# 15_RS485.net
KiCad netlist of a schematic drawn in Altium Designer
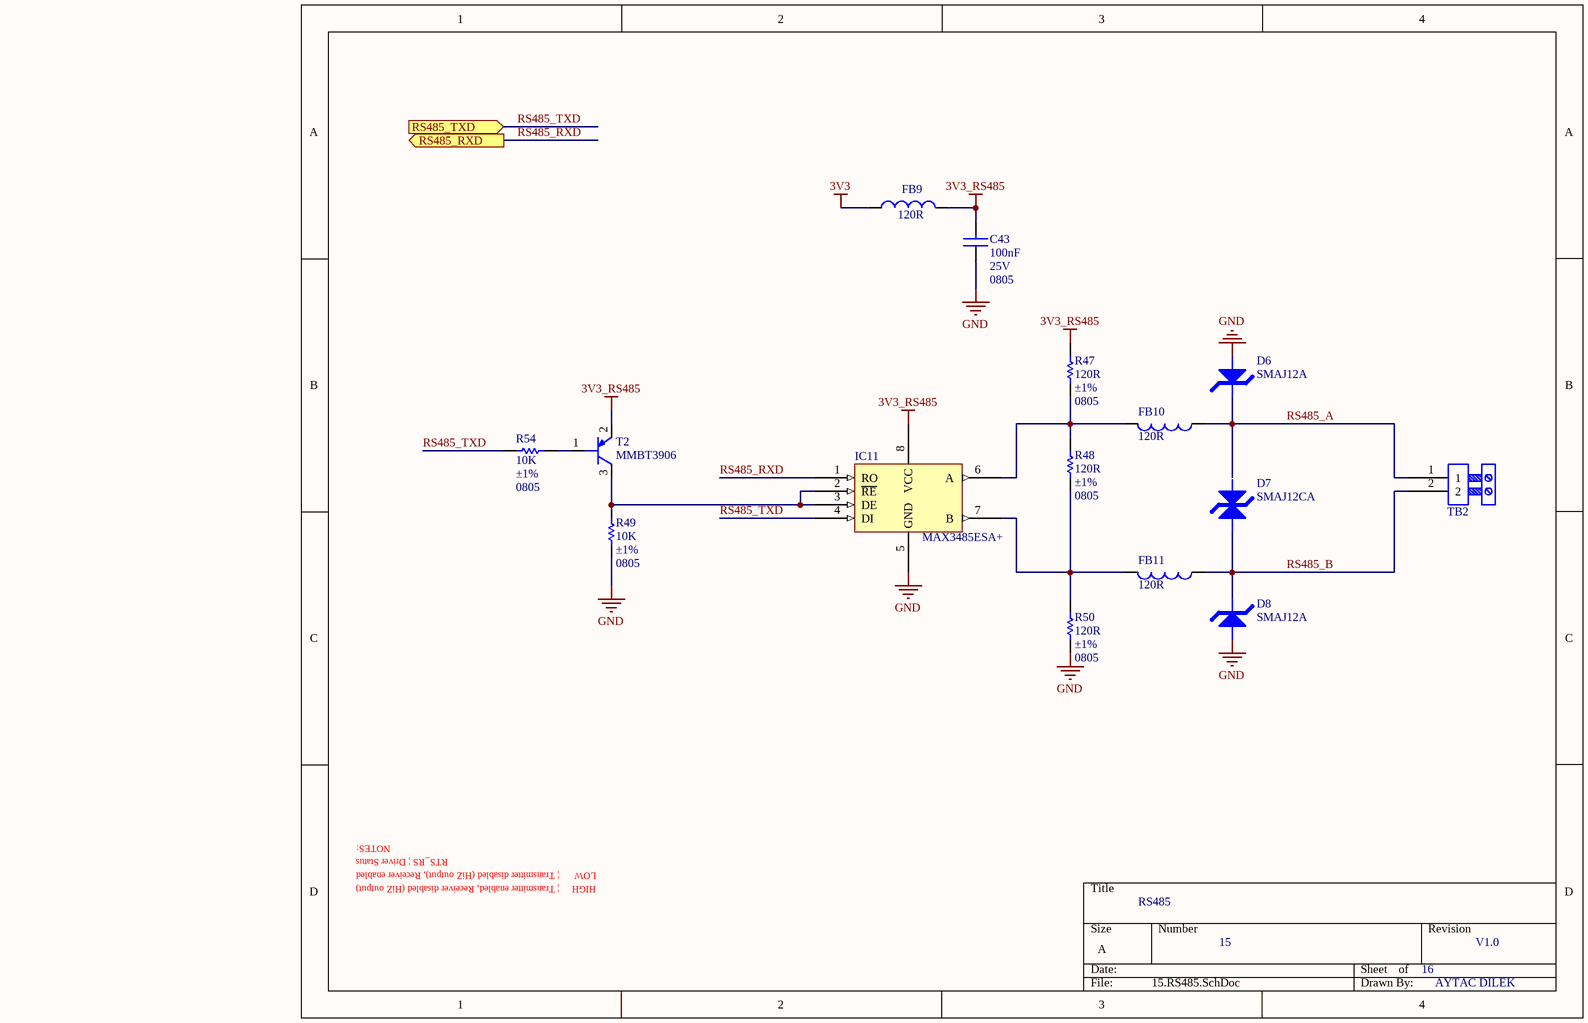
[diagram p0: 15.RS485.SchDoc]

(export (version "E")
  (design (tool "Eeschema 10.0.6"))
  (components
    (comp (ref "C43")
      (value "CAP_NP")
      (footprint "CAPC2012X100N_EIA0805")
      (description "CAP CER 0.1UF 25V X7R 0805")
      (fields
        (field (name "PART NUMBER") "SCAP00300093")
        (field (name "CAPACITANCE") "100nF")
        (field (name "TOLERANCE") "±10%")
        (field (name "VOLTAGE - RATED") "25V")
        (field (name "PACKAGE / CASE") "0805")
      )
      (libsource (lib "ComponentDatabase") (part "CAP_NP"))
    )
    (comp (ref "D6")
      (value "SMAJ12A")
      (footprint "DIOM5126X26N_DO-214AC_SMA")
      (description "TVS DIODE 12VWM 19.9VC SMA")
      (fields (field (name "PART NUMBER") "SCP00005") (field (name "MANUFACTURER") "Littelfuse Inc."))
      (libsource (lib "ComponentDatabase") (part "DIODE_TVS_UNI"))
    )
    (comp (ref "D7")
      (value "SMAJ12CA")
      (footprint "DIOM5126X26N_DO-214AC_SMA")
      (description "TVS DIODE 12VWM 19.9VC SMA")
      (fields (field (name "PART NUMBER") "SCP00006") (field (name "MANUFACTURER") "Littelfuse Inc."))
      (libsource (lib "ComponentDatabase") (part "DIODE_TVS_BI"))
    )
    (comp (ref "D8")
      (value "SMAJ12A")
      (footprint "DIOM5126X26N_DO-214AC_SMA")
      (description "TVS DIODE 12VWM 19.9VC SMA")
      (fields (field (name "PART NUMBER") "SCP00005") (field (name "MANUFACTURER") "Littelfuse Inc."))
      (libsource (lib "ComponentDatabase") (part "DIODE_TVS_UNI"))
    )
    (comp (ref "FB9")
      (value "BEAD")
      (footprint "FILC2012X100N_EIA0805")
      (description "FERRITE CHIP POWER 120 OHM SMD")
      (fields
        (field (name "PART NUMBER") "SFIL00005")
        (field (name "IMPEDANCE") "120R")
        (field (name "MANUFACTURER") "Laird-Signal Integrity Products")
      )
      (libsource (lib "ComponentDatabase") (part "BEAD"))
    )
    (comp (ref "FB10")
      (value "BEAD")
      (footprint "FILC2012X100N_EIA0805")
      (description "FERRITE CHIP POWER 120 OHM SMD")
      (fields
        (field (name "PART NUMBER") "SFIL00005")
        (field (name "IMPEDANCE") "120R")
        (field (name "MANUFACTURER") "Laird-Signal Integrity Products")
      )
      (libsource (lib "ComponentDatabase") (part "BEAD"))
    )
    (comp (ref "FB11")
      (value "BEAD")
      (footprint "FILC2012X100N_EIA0805")
      (description "FERRITE CHIP POWER 120 OHM SMD")
      (fields
        (field (name "PART NUMBER") "SFIL00005")
        (field (name "IMPEDANCE") "120R")
        (field (name "MANUFACTURER") "Laird-Signal Integrity Products")
      )
      (libsource (lib "ComponentDatabase") (part "BEAD"))
    )
    (comp (ref "IC11")
      (value "MAX3485")
      (footprint "SOIC127P600X175-8N")
      (description "IC TXRX RS485/422 10MBPS 8SOIC")
      (fields
        (field (name "PART NUMBER") "SIC00035")
        (field (name "MANUFACTURER PART NUMBER") "MAX3485ESA+")
        (field (name "MANUFACTURER") "Maxim Integrated")
      )
      (libsource (lib "ComponentDatabase") (part "MAX3485"))
    )
    (comp (ref "R47")
      (value "120R")
      (footprint "RESC2013X65N_EIA0805")
      (description "RES SMD 120 OHM 1% 1/8W 0805")
      (fields
        (field (name "PART NUMBER") "SRES03010052")
        (field (name "TOLERANCE") "±1%")
        (field (name "PACKAGE / CASE") "0805")
        (field (name "MANUFACTURER") "Yageo")
      )
      (libsource (lib "ComponentDatabase") (part "RES"))
    )
    (comp (ref "R48")
      (value "120R")
      (footprint "RESC2013X65N_EIA0805")
      (description "RES SMD 120 OHM 1% 1/8W 0805")
      (fields
        (field (name "PART NUMBER") "SRES03010052")
        (field (name "TOLERANCE") "±1%")
        (field (name "PACKAGE / CASE") "0805")
        (field (name "MANUFACTURER") "Yageo")
      )
      (libsource (lib "ComponentDatabase") (part "RES"))
    )
    (comp (ref "R49")
      (value "10K")
      (footprint "RESC2013X65N_EIA0805")
      (description "RES SMD 10K OHM 1% 1/8W 0805")
      (fields
        (field (name "PART NUMBER") "SRES03010098")
        (field (name "TOLERANCE") "±1%")
        (field (name "PACKAGE / CASE") "0805")
        (field (name "MANUFACTURER") "Yageo")
      )
      (libsource (lib "ComponentDatabase") (part "RES"))
    )
    (comp (ref "R50")
      (value "120R")
      (footprint "RESC2013X65N_EIA0805")
      (description "RES SMD 120 OHM 1% 1/8W 0805")
      (fields
        (field (name "PART NUMBER") "SRES03010052")
        (field (name "TOLERANCE") "±1%")
        (field (name "PACKAGE / CASE") "0805")
        (field (name "MANUFACTURER") "Yageo")
      )
      (libsource (lib "ComponentDatabase") (part "RES"))
    )
    (comp (ref "R54")
      (value "10K")
      (footprint "RESC2013X65N_EIA0805")
      (description "RES SMD 10K OHM 1% 1/8W 0805")
      (fields
        (field (name "PART NUMBER") "SRES03010098")
        (field (name "TOLERANCE") "±1%")
        (field (name "PACKAGE / CASE") "0805")
        (field (name "MANUFACTURER") "Yageo")
      )
      (libsource (lib "ComponentDatabase") (part "RES"))
    )
    (comp (ref "T2")
      (value "MMBT3906")
      (footprint "SOT95P240X120-3N_SOT-23-3")
      (description "TRANS PNP 40V 0.2A SOT-23")
      (fields
        (field (name "PART NUMBER") "SSEM00023")
        (field (name "MANUFACTURER") "Fairchild Semiconductor")
      )
      (libsource (lib "ComponentDatabase") (part "MMBT3906"))
    )
    (comp (ref "TB2")
      (value "TB2_EURO")
      (footprint "TB2_EURO")
      (description "TERM BLOCK HDR 2POS VERT 3.81MM")
      (fields
        (field (name "PART NUMBER") "SCON00138")
        (field (name "MANUFACTURER") "On Shore Technology Inc.")
      )
      (libsource (lib "ComponentDatabase") (part "TB2_EURO"))
    )
  )
  (nets
    (net (code "1") (name "/RS485_A") (class "Default")
      (node (ref "D6") (pin "1") (pinfunction "1_1") (pintype "passive"))
      (node (ref "D7") (pin "1") (pinfunction "1_1") (pintype "passive"))
      (node (ref "FB10") (pin "1") (pinfunction "1_1") (pintype "passive"))
      (node (ref "TB2") (pin "1") (pinfunction "1_1") (pintype "power_in"))
    )
    (net (code "2") (name "/RS485_B") (class "Default")
      (node (ref "D7") (pin "2") (pinfunction "2_2") (pintype "passive"))
      (node (ref "D8") (pin "1") (pinfunction "1_1") (pintype "passive"))
      (node (ref "FB11") (pin "1") (pinfunction "1_1") (pintype "passive"))
      (node (ref "TB2") (pin "2") (pinfunction "2_2") (pintype "power_in"))
    )
    (net (code "3") (name "/RS485_RXD") (class "Default")
      (node (ref "IC11") (pin "1") (pinfunction "RO_1") (pintype "input"))
    )
    (net (code "4") (name "/RS485_TXD") (class "Default")
      (node (ref "IC11") (pin "4") (pinfunction "DI_4") (pintype "input"))
      (node (ref "R54") (pin "1") (pinfunction "1_1") (pintype "passive"))
    )
    (net (code "5") (name "3V3") (class "Default")
      (node (ref "FB9") (pin "1") (pinfunction "1_1") (pintype "passive"))
    )
    (net (code "6") (name "3V3_RS485") (class "Default")
      (node (ref "C43") (pin "2") (pinfunction "2_2") (pintype "passive"))
      (node (ref "FB9") (pin "2") (pinfunction "2_2") (pintype "passive"))
      (node (ref "IC11") (pin "8") (pinfunction "VCC_8") (pintype "power_in"))
      (node (ref "R47") (pin "1") (pinfunction "1_1") (pintype "passive"))
      (node (ref "T2") (pin "2") (pinfunction "E_2") (pintype "passive"))
    )
    (net (code "7") (name "GND") (class "Default")
      (node (ref "C43") (pin "1") (pinfunction "1_1") (pintype "passive"))
      (node (ref "D6") (pin "2") (pinfunction "2_2") (pintype "passive"))
      (node (ref "D8") (pin "2") (pinfunction "2_2") (pintype "passive"))
      (node (ref "IC11") (pin "5") (pinfunction "GND_5") (pintype "power_in"))
      (node (ref "R49") (pin "2") (pinfunction "2_2") (pintype "passive"))
      (node (ref "R50") (pin "2") (pinfunction "2_2") (pintype "passive"))
    )
    (net (code "8") (name "Net-(IC11-A)") (class "Default")
      (node (ref "FB10") (pin "2") (pinfunction "2_2") (pintype "passive"))
      (node (ref "IC11") (pin "6") (pinfunction "A_6") (pintype "output"))
      (node (ref "R47") (pin "2") (pinfunction "2_2") (pintype "passive"))
      (node (ref "R48") (pin "1") (pinfunction "1_1") (pintype "passive"))
    )
    (net (code "9") (name "Net-(IC11-B)") (class "Default")
      (node (ref "FB11") (pin "2") (pinfunction "2_2") (pintype "passive"))
      (node (ref "IC11") (pin "7") (pinfunction "B_7") (pintype "output"))
      (node (ref "R48") (pin "2") (pinfunction "2_2") (pintype "passive"))
      (node (ref "R50") (pin "1") (pinfunction "1_1") (pintype "passive"))
    )
    (net (code "10") (name "Net-(IC11-DE)") (class "Default")
      (node (ref "IC11") (pin "2") (pinfunction "~{RE}_2") (pintype "input"))
      (node (ref "IC11") (pin "3") (pinfunction "DE_3") (pintype "input"))
      (node (ref "R49") (pin "1") (pinfunction "1_1") (pintype "passive"))
      (node (ref "T2") (pin "3") (pinfunction "C_3") (pintype "passive"))
    )
    (net (code "11") (name "Net-(T2-B)") (class "Default")
      (node (ref "R54") (pin "2") (pinfunction "2_2") (pintype "passive"))
      (node (ref "T2") (pin "1") (pinfunction "B_1") (pintype "passive"))
    )
  )
)
